# Sheet2.net
KiCad netlist of a schematic drawn in Altium Designer
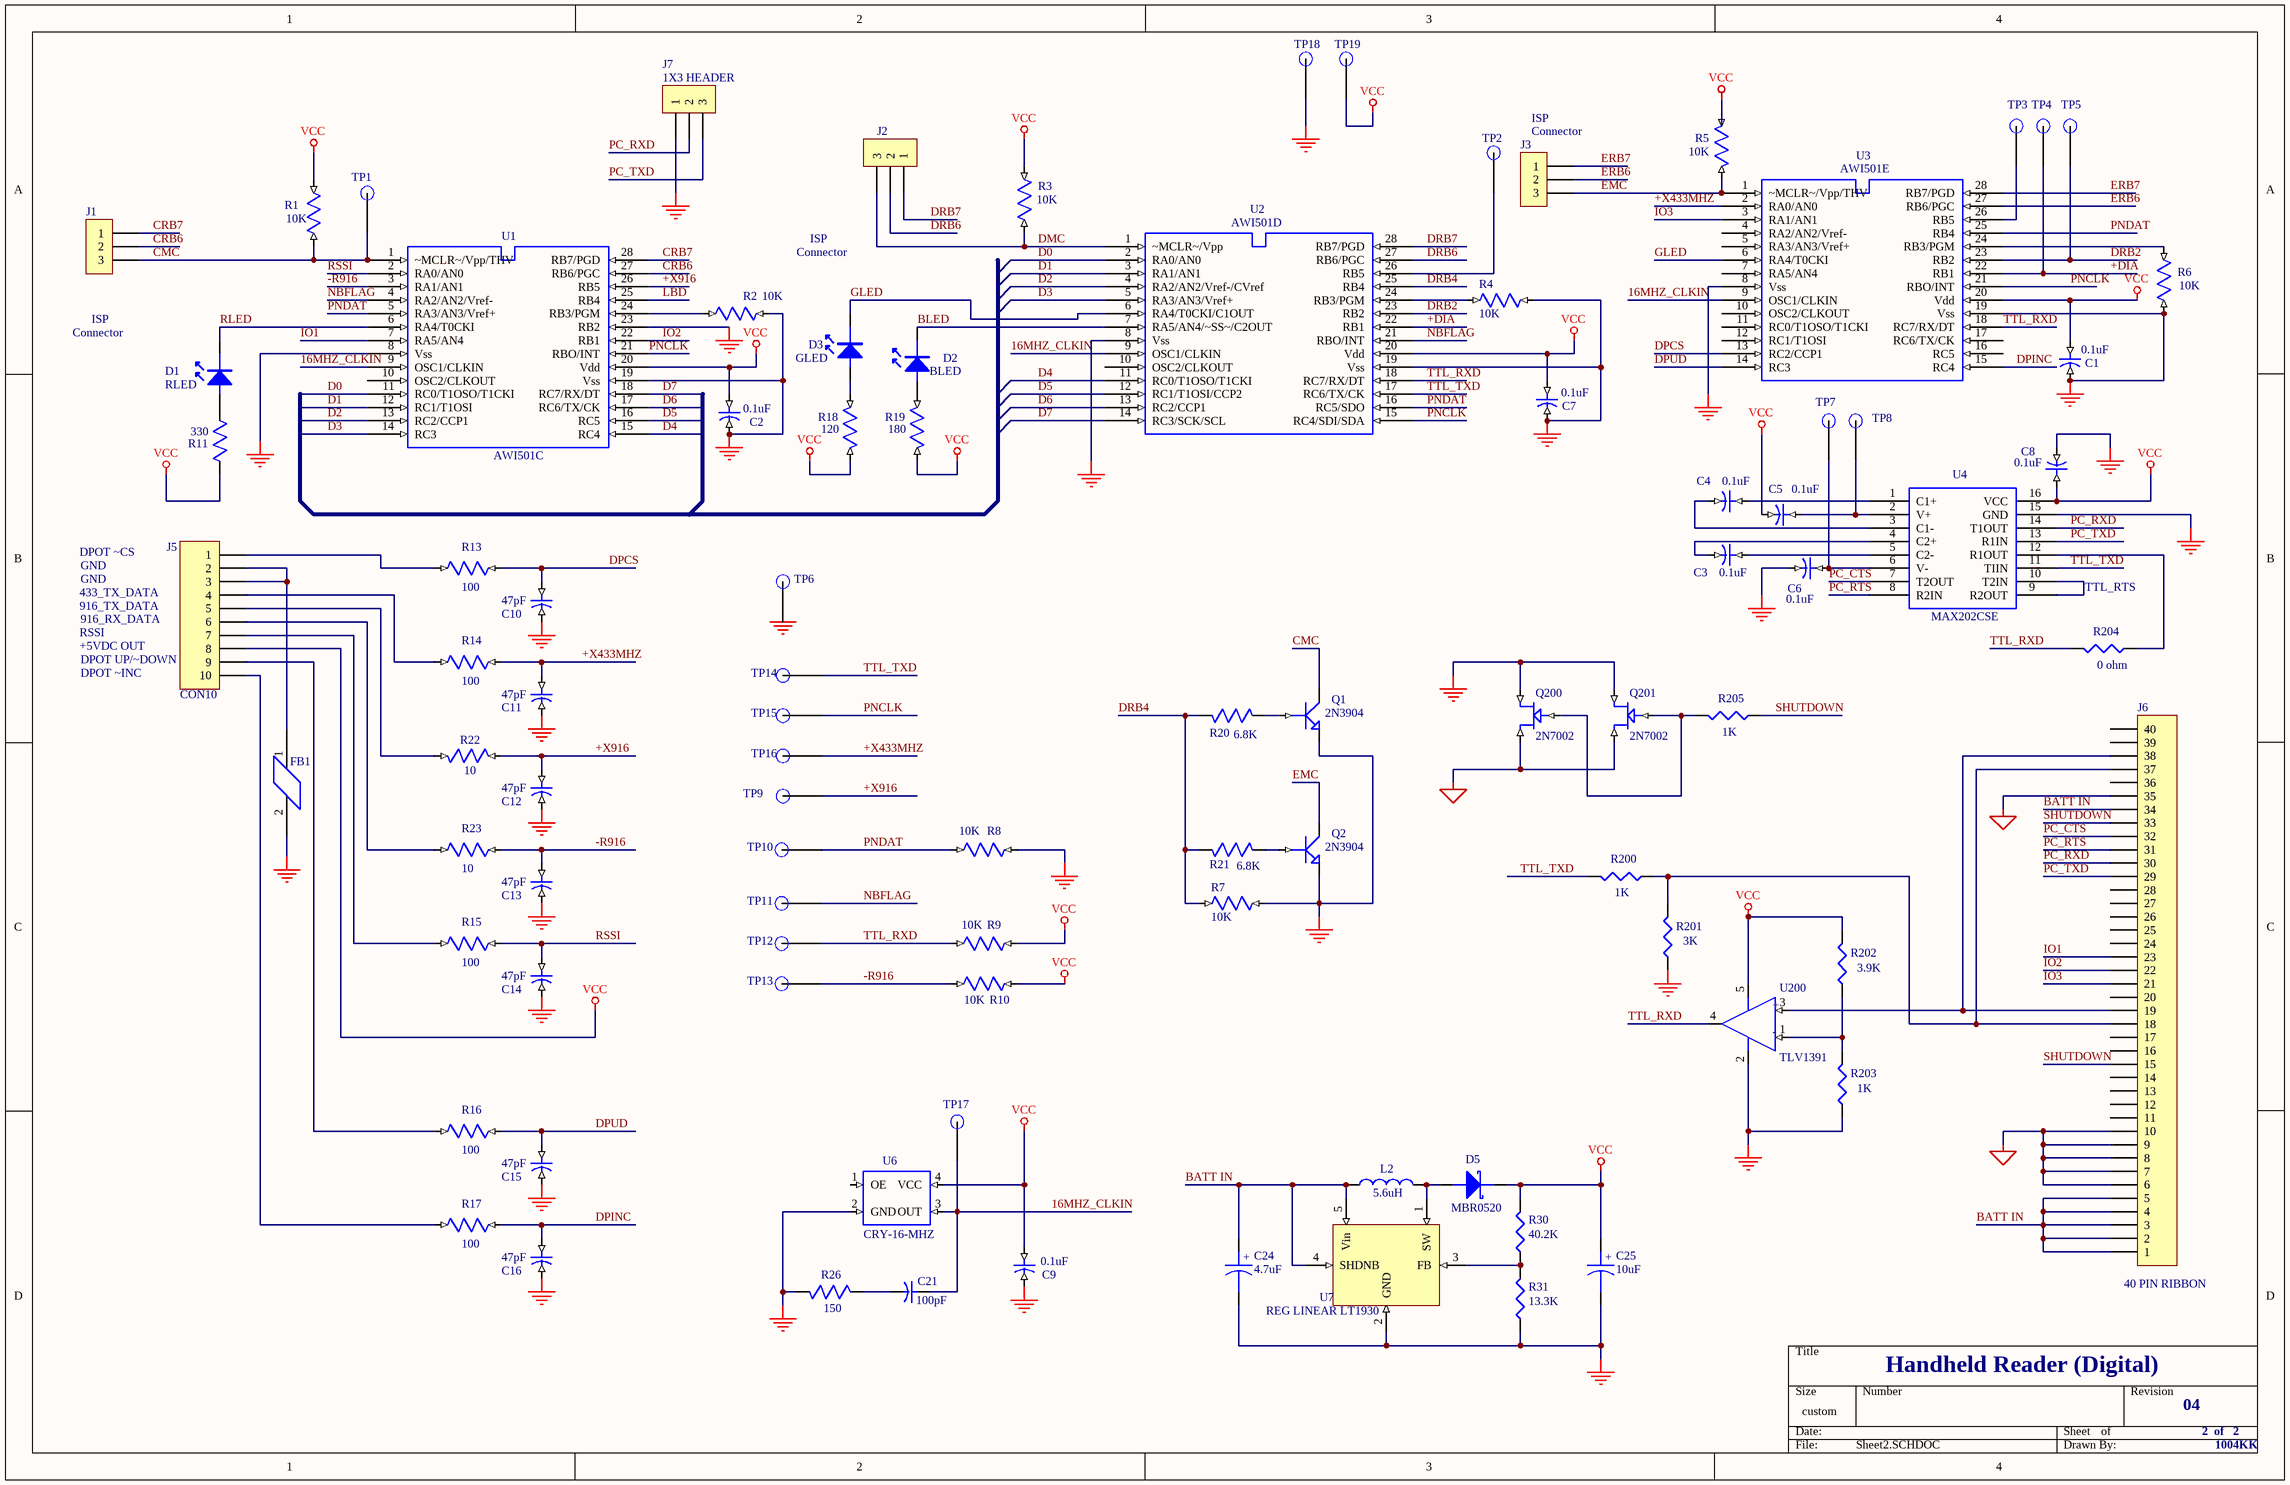
[diagram p0: Sheet2.SCHDOC]

(export (version "E")
  (design (tool "Eeschema 10.0.6"))
  (components
    (comp (ref "C1") (value "0.1uF") (footprint "0603") (libsource (lib "*") (part "C_603")))
    (comp (ref "C2") (value "0.1uF") (footprint "0603") (libsource (lib "*") (part "C_603")))
    (comp (ref "C3") (value "0.1uF") (footprint "0603") (libsource (lib "") (part "C_603_1")))
    (comp (ref "C4") (value "0.1uF") (footprint "0603") (libsource (lib "") (part "C_603_1")))
    (comp (ref "C5") (value "0.1uF") (footprint "0603") (libsource (lib "") (part "C_603_1")))
    (comp (ref "C6") (value "0.1uF") (footprint "0603") (libsource (lib "") (part "C_603_1")))
    (comp (ref "C7") (value "0.1uF") (footprint "0603") (libsource (lib "*") (part "C_603")))
    (comp (ref "C8") (value "0.1uF") (footprint "0603") (libsource (lib "") (part "C_603_1")))
    (comp (ref "C9") (value "0.1uF") (footprint "0603") (libsource (lib "") (part "C_603_1")))
    (comp (ref "C10") (value "47pF") (footprint "0603") (libsource (lib "*") (part "C0603")))
    (comp (ref "C11") (value "47pF") (footprint "0603") (libsource (lib "*") (part "C0603")))
    (comp (ref "C12") (value "47pF") (footprint "0603") (libsource (lib "*") (part "C0603")))
    (comp (ref "C13") (value "47pF") (footprint "0603") (libsource (lib "*") (part "C0603")))
    (comp (ref "C14") (value "47pF") (footprint "0603") (libsource (lib "*") (part "C0603")))
    (comp (ref "C15") (value "47pF") (footprint "0603") (libsource (lib "*") (part "C0603")))
    (comp (ref "C16") (value "47pF") (footprint "0603") (libsource (lib "*") (part "C0603")))
    (comp (ref "C21") (value "100pF") (footprint "0603") (libsource (lib "*") (part "C_0603")))
    (comp (ref "C24")
      (value "4.7uF")
      (footprint "CAP A CASE")
      (description "Capacitor")
      (libsource (lib "*") (part "CAPACITOR POL"))
    )
    (comp (ref "C25")
      (value "10uF")
      (footprint "CAP A CASE")
      (description "Capacitor")
      (libsource (lib "*") (part "CAPACITOR POL"))
    )
    (comp (ref "D1") (value "RLED") (footprint "SOD123 DIODE") (libsource (lib "*") (part "LED")))
    (comp (ref "D2") (value "BLED") (footprint "SOD123 DIODE") (libsource (lib "*") (part "LED")))
    (comp (ref "D3") (value "GLED") (footprint "SOD123 DIODE") (libsource (lib "*") (part "LED")))
    (comp (ref "D5")
      (value "MBR0520")
      (footprint "SOD123")
      (description "Schottky Diode")
      (libsource (lib "*") (part "DIODE SCHOTTKY"))
    )
    (comp (ref "FB1") (value "FB 0603") (footprint "0603") (libsource (lib "*") (part "FB_0603")))
    (comp (ref "J1")
      (value "1X3 HEADER")
      (footprint "1X3 HEADER")
      (description "Connector")
      (libsource (lib "*") (part "CON3"))
    )
    (comp (ref "J2")
      (value "1X3 HEADER")
      (footprint "1X3 HEADER")
      (description "Connector")
      (libsource (lib "") (part "CON3_2"))
    )
    (comp (ref "J3")
      (value "1X3 HEADER")
      (footprint "1X3 HEADER")
      (description "Connector")
      (libsource (lib "*") (part "CON3"))
    )
    (comp (ref "J5")
      (value "CON10")
      (footprint "1X10 HEADER SPECIAL")
      (description "Connector")
      (libsource (lib "*") (part "CON10"))
    )
    (comp (ref "J6")
      (value "40 PIN RIBBON")
      (footprint "40 PIN RIBBON CONN")
      (description "Connector")
      (libsource (lib "*") (part "CON40"))
    )
    (comp (ref "J7")
      (value "1X3 HEADER")
      (footprint "1X3 HEADER")
      (description "Connector")
      (libsource (lib "") (part "CON3_1"))
    )
    (comp (ref "L2")
      (value "5.6uH")
      (footprint "COIL BOURNS SDR7030-330M")
      (libsource (lib "*") (part "INDUCTOR1"))
    )
    (comp (ref "Q1")
      (value "2N3904")
      (footprint "SOT23 TRANS")
      (description "NPN Transistor")
      (libsource (lib "*") (part "NPN1"))
    )
    (comp (ref "Q2")
      (value "2N3904")
      (footprint "SOT23 TRANS")
      (description "NPN Transistor")
      (libsource (lib "*") (part "NPN1"))
    )
    (comp (ref "Q200") (value "2N7002") (footprint "SOT23 FET") (libsource (lib "*") (part "JFET N")))
    (comp (ref "Q201") (value "2N7002") (footprint "SOT23 FET") (libsource (lib "*") (part "JFET N")))
    (comp (ref "R1") (value "10K") (footprint "0603") (libsource (lib "*") (part "R_603")))
    (comp (ref "R2") (value "10K") (footprint "0603") (libsource (lib "*") (part "R_603")))
    (comp (ref "R3") (value "10K") (footprint "0603") (libsource (lib "*") (part "R_603")))
    (comp (ref "R4") (value "10K") (footprint "0603") (libsource (lib "*") (part "R_603")))
    (comp (ref "R5") (value "10K") (footprint "0603") (libsource (lib "*") (part "R_603")))
    (comp (ref "R6") (value "10K") (footprint "0603") (libsource (lib "*") (part "R_603")))
    (comp (ref "R7") (value "10K") (footprint "0603") (libsource (lib "*") (part "R_603")))
    (comp (ref "R8") (value "10K") (footprint "0603") (libsource (lib "*") (part "R_603")))
    (comp (ref "R9") (value "10K") (footprint "0603") (libsource (lib "*") (part "R_603")))
    (comp (ref "R10") (value "10K") (footprint "0603") (libsource (lib "*") (part "R_603")))
    (comp (ref "R11") (value "330") (footprint "0603") (libsource (lib "*") (part "R_0603")))
    (comp (ref "R13") (value "100") (footprint "0603") (libsource (lib "*") (part "R0603")))
    (comp (ref "R14") (value "100") (footprint "0603") (libsource (lib "*") (part "R0603")))
    (comp (ref "R15") (value "100") (footprint "0603") (libsource (lib "*") (part "R0603")))
    (comp (ref "R16") (value "100") (footprint "0603") (libsource (lib "*") (part "R0603")))
    (comp (ref "R17") (value "100") (footprint "0603") (libsource (lib "*") (part "R0603")))
    (comp (ref "R18") (value "120") (footprint "0603") (libsource (lib "*") (part "R0402")))
    (comp (ref "R19") (value "180") (footprint "0603") (libsource (lib "*") (part "R0402")))
    (comp (ref "R20") (value "6.8K") (footprint "0603") (libsource (lib "*") (part "R_0603")))
    (comp (ref "R21") (value "6.8K") (footprint "0603") (libsource (lib "*") (part "R_0603")))
    (comp (ref "R22") (value "10") (footprint "0603") (libsource (lib "*") (part "R_603")))
    (comp (ref "R23") (value "10") (footprint "0603") (libsource (lib "*") (part "R0603")))
    (comp (ref "R26") (value "150") (footprint "0603") (libsource (lib "*") (part "R_0603")))
    (comp (ref "R30") (value "40.2K") (footprint "0603") (libsource (lib "*") (part "RES1")))
    (comp (ref "R31") (value "13.3K") (footprint "0603") (libsource (lib "*") (part "RES1")))
    (comp (ref "R200") (value "1K") (footprint "0603") (libsource (lib "*") (part "RES1")))
    (comp (ref "R201") (value "3K") (footprint "0603") (libsource (lib "*") (part "RES1")))
    (comp (ref "R202") (value "3.9K") (footprint "0603") (libsource (lib "*") (part "RES1")))
    (comp (ref "R203") (value "1K") (footprint "0603") (libsource (lib "*") (part "RES1")))
    (comp (ref "R204") (value "0 ohm") (footprint "0603") (libsource (lib "*") (part "RES1")))
    (comp (ref "R205") (value "1K") (footprint "0603") (libsource (lib "*") (part "RES1")))
    (comp (ref "TP1") (value "TP") (footprint "TEST POINT PAD") (libsource (lib "*") (part "TESTPOINT_1")))
    (comp (ref "TP2") (value "TP") (footprint "TEST POINT PAD") (libsource (lib "*") (part "TESTPOINT_1")))
    (comp (ref "TP3") (value "TP") (footprint "TEST POINT PAD") (libsource (lib "*") (part "TESTPOINT_1")))
    (comp (ref "TP4") (value "TP") (footprint "TEST POINT PAD") (libsource (lib "*") (part "TESTPOINT_1")))
    (comp (ref "TP5") (value "TP") (footprint "TEST POINT PAD") (libsource (lib "*") (part "TESTPOINT_1")))
    (comp (ref "TP6") (value "TP") (footprint "TEST POINT PAD") (libsource (lib "*") (part "TESTPOINT_1")))
    (comp (ref "TP7") (value "TP") (footprint "TEST POINT PAD") (libsource (lib "*") (part "TESTPOINT_1")))
    (comp (ref "TP8") (value "TP") (footprint "TEST POINT PAD") (libsource (lib "*") (part "TESTPOINT_1")))
    (comp (ref "TP9") (value "TP") (footprint "TEST POINT PAD") (libsource (lib "*") (part "TESTPOINT_1")))
    (comp (ref "TP10") (value "TP") (footprint "TEST POINT PAD") (libsource (lib "*") (part "TESTPOINT_1")))
    (comp (ref "TP11") (value "TP") (footprint "TEST POINT PAD") (libsource (lib "*") (part "TESTPOINT_1")))
    (comp (ref "TP12") (value "TP") (footprint "TEST POINT PAD") (libsource (lib "*") (part "TESTPOINT_1")))
    (comp (ref "TP13") (value "TP") (footprint "TEST POINT PAD") (libsource (lib "*") (part "TESTPOINT_1")))
    (comp (ref "TP14") (value "TP") (footprint "TEST POINT PAD") (libsource (lib "*") (part "TESTPOINT_1")))
    (comp (ref "TP15") (value "TP") (footprint "TEST POINT PAD") (libsource (lib "*") (part "TESTPOINT_1")))
    (comp (ref "TP16") (value "TP") (footprint "TEST POINT PAD") (libsource (lib "*") (part "TESTPOINT_1")))
    (comp (ref "TP17") (value "TP") (footprint "TEST POINT PAD") (libsource (lib "*") (part "TESTPOINT_1")))
    (comp (ref "TP18") (value "TP") (footprint "TEST POINT PAD") (libsource (lib "*") (part "TESTPOINT_1")))
    (comp (ref "TP19") (value "TP") (footprint "TEST POINT PAD") (libsource (lib "*") (part "TESTPOINT_1")))
    (comp (ref "U1") (value "AWI501C") (footprint "SSOP28") (libsource (lib "*") (part "PIC16F870")))
    (comp (ref "U2") (value "AWI501D") (footprint "SSOP28") (libsource (lib "*") (part "PIC16F876A")))
    (comp (ref "U3") (value "AWI501E") (footprint "SSOP28") (libsource (lib "*") (part "PIC16F870")))
    (comp (ref "U4") (value "MAX202CSE") (footprint "SO16") (libsource (lib "*") (part "MAX202CSE")))
    (comp (ref "U6")
      (value "CRY-16-MHZ")
      (footprint "SMT OSCILLATOR")
      (libsource (lib "*") (part "CRY-SMD-5-7"))
    )
    (comp (ref "U7")
      (value "REG LINEAR LT1930")
      (footprint "SOT23-5A")
      (libsource (lib "*") (part "REG LINEAR LT1930"))
    )
    (comp (ref "U200") (value "TLV1391") (footprint "SOT25") (libsource (lib "*") (part "TLV1391")))
  )
  (nets
    (net (code "1") (name "/+DIA") (class "Default")
      (node (ref "TP4") (pin "1") (pinfunction "TP_1") (pintype "passive"))
      (node (ref "U2") (pin "22") (pinfunction "RB1_22") (pintype "input"))
      (node (ref "U3") (pin "22") (pinfunction "RB1_22") (pintype "input"))
    )
    (net (code "2") (name "/+X433MHZ") (class "Default")
      (node (ref "C11") (pin "1") (pinfunction "A_1") (pintype "input"))
      (node (ref "R14") (pin "2") (pinfunction "B_2") (pintype "input"))
      (node (ref "TP16") (pin "1") (pinfunction "TP_1") (pintype "passive"))
      (node (ref "U3") (pin "2") (pinfunction "RA0/AN0_2") (pintype "input"))
    )
    (net (code "3") (name "/+X916") (class "Default")
      (node (ref "C12") (pin "1") (pinfunction "A_1") (pintype "input"))
      (node (ref "R22") (pin "1") (pinfunction "A_1") (pintype "input"))
      (node (ref "TP9") (pin "1") (pinfunction "TP_1") (pintype "passive"))
      (node (ref "U1") (pin "26") (pinfunction "RB5_26") (pintype "input"))
    )
    (net (code "4") (name "/-R916") (class "Default")
      (node (ref "C13") (pin "1") (pinfunction "A_1") (pintype "input"))
      (node (ref "R10") (pin "2") (pinfunction "B_2") (pintype "input"))
      (node (ref "R23") (pin "2") (pinfunction "B_2") (pintype "input"))
      (node (ref "TP13") (pin "1") (pinfunction "TP_1") (pintype "passive"))
      (node (ref "U1") (pin "3") (pinfunction "RA1/AN1_3") (pintype "input"))
    )
    (net (code "5") (name "/16MHZ_CLKIN") (class "Default")
      (node (ref "C21") (pin "1") (pinfunction "A_1") (pintype "passive"))
      (node (ref "TP17") (pin "1") (pinfunction "TP_1") (pintype "passive"))
      (node (ref "U1") (pin "9") (pinfunction "OSC1/CLKIN_9") (pintype "input"))
      (node (ref "U2") (pin "9") (pinfunction "OSC1/CLKIN_9") (pintype "input"))
      (node (ref "U3") (pin "9") (pinfunction "OSC1/CLKIN_9") (pintype "input"))
      (node (ref "U6") (pin "3") (pinfunction "OUT_3") (pintype "input"))
    )
    (net (code "6") (name "/BATT IN") (class "Default")
      (node (ref "C24") (pin "1") (pinfunction "1_1") (pintype "passive"))
      (node (ref "J6") (pin "1") (pinfunction "1_1") (pintype "passive"))
      (node (ref "J6") (pin "2") (pinfunction "2_2") (pintype "passive"))
      (node (ref "J6") (pin "3") (pinfunction "3_3") (pintype "passive"))
      (node (ref "J6") (pin "34") (pinfunction "34_34") (pintype "passive"))
      (node (ref "J6") (pin "4") (pinfunction "4_4") (pintype "passive"))
      (node (ref "J6") (pin "5") (pinfunction "5_5") (pintype "passive"))
      (node (ref "L2") (pin "1") (pinfunction "1_1") (pintype "passive"))
      (node (ref "U7") (pin "4") (pinfunction "SHDNB_4") (pintype "input"))
      (node (ref "U7") (pin "5") (pinfunction "Vin_5") (pintype "input"))
    )
    (net (code "7") (name "/BLED") (class "Default")
      (node (ref "D2") (pin "K") (pinfunction "K_K") (pintype "passive"))
      (node (ref "U2") (pin "7") (pinfunction "RA5/AN4/~SS~/C2OUT_7") (pintype "input"))
    )
    (net (code "8") (name "/CMC") (class "Default")
      (node (ref "J1") (pin "3") (pinfunction "3_3") (pintype "passive"))
      (node (ref "Q1") (pin "C") (pinfunction "C_C") (pintype "passive"))
      (node (ref "R1") (pin "2") (pinfunction "B_2") (pintype "input"))
      (node (ref "TP1") (pin "1") (pinfunction "TP_1") (pintype "passive"))
      (node (ref "U1") (pin "1") (pinfunction "~MCLR~/Vpp/THV_1") (pintype "input"))
    )
    (net (code "9") (name "/CRB6") (class "Default")
      (node (ref "J1") (pin "2") (pinfunction "2_2") (pintype "passive"))
      (node (ref "U1") (pin "27") (pinfunction "RB6/PGC_27") (pintype "input"))
    )
    (net (code "10") (name "/CRB7") (class "Default")
      (node (ref "J1") (pin "1") (pinfunction "1_1") (pintype "passive"))
      (node (ref "U1") (pin "28") (pinfunction "RB7/PGD_28") (pintype "input"))
    )
    (net (code "11") (name "/D0") (class "Default")
      (node (ref "U1") (pin "11") (pinfunction "RC0/T1OSO/T1CKI_11") (pintype "input"))
      (node (ref "U2") (pin "2") (pinfunction "RA0/AN0_2") (pintype "input"))
    )
    (net (code "12") (name "/D1") (class "Default")
      (node (ref "U1") (pin "12") (pinfunction "RC1/T1OSI_12") (pintype "input"))
      (node (ref "U2") (pin "3") (pinfunction "RA1/AN1_3") (pintype "input"))
    )
    (net (code "13") (name "/D2") (class "Default")
      (node (ref "U1") (pin "13") (pinfunction "RC2/CCP1_13") (pintype "input"))
      (node (ref "U2") (pin "4") (pinfunction "RA2/AN2/Vref-/CVref_4") (pintype "input"))
    )
    (net (code "14") (name "/D3") (class "Default")
      (node (ref "U1") (pin "14") (pinfunction "RC3_14") (pintype "input"))
      (node (ref "U2") (pin "5") (pinfunction "RA3/AN3/Vref+_5") (pintype "input"))
    )
    (net (code "15") (name "/D4") (class "Default")
      (node (ref "U1") (pin "15") (pinfunction "RC4_15") (pintype "input"))
      (node (ref "U2") (pin "11") (pinfunction "RC0/T1OSO/T1CKI_11") (pintype "input"))
    )
    (net (code "16") (name "/D5") (class "Default")
      (node (ref "U1") (pin "16") (pinfunction "RC5_16") (pintype "input"))
      (node (ref "U2") (pin "12") (pinfunction "RC1/T1OSI/CCP2_12") (pintype "input"))
    )
    (net (code "17") (name "/D6") (class "Default")
      (node (ref "U1") (pin "17") (pinfunction "RC6/TX/CK_17") (pintype "input"))
      (node (ref "U2") (pin "13") (pinfunction "RC2/CCP1_13") (pintype "input"))
    )
    (net (code "18") (name "/D7") (class "Default")
      (node (ref "U1") (pin "18") (pinfunction "RC7/RX/DT_18") (pintype "input"))
      (node (ref "U2") (pin "14") (pinfunction "RC3/SCK/SCL_14") (pintype "input"))
    )
    (net (code "19") (name "/DMC") (class "Default")
      (node (ref "J2") (pin "3") (pinfunction "3_3") (pintype "passive"))
      (node (ref "R3") (pin "2") (pinfunction "B_2") (pintype "input"))
      (node (ref "U2") (pin "1") (pinfunction "~MCLR~/Vpp_1") (pintype "input"))
    )
    (net (code "20") (name "/DPCS") (class "Default")
      (node (ref "C10") (pin "1") (pinfunction "A_1") (pintype "input"))
      (node (ref "R13") (pin "2") (pinfunction "B_2") (pintype "input"))
      (node (ref "U3") (pin "13") (pinfunction "RC2/CCP1_13") (pintype "input"))
    )
    (net (code "21") (name "/DPINC") (class "Default")
      (node (ref "C16") (pin "1") (pinfunction "A_1") (pintype "input"))
      (node (ref "R17") (pin "2") (pinfunction "B_2") (pintype "input"))
      (node (ref "U3") (pin "15") (pinfunction "RC4_15") (pintype "input"))
    )
    (net (code "22") (name "/DPUD") (class "Default")
      (node (ref "C15") (pin "1") (pinfunction "A_1") (pintype "input"))
      (node (ref "R16") (pin "2") (pinfunction "B_2") (pintype "input"))
      (node (ref "U3") (pin "14") (pinfunction "RC3_14") (pintype "input"))
    )
    (net (code "23") (name "/DRB2") (class "Default")
      (node (ref "TP5") (pin "1") (pinfunction "TP_1") (pintype "passive"))
      (node (ref "U2") (pin "23") (pinfunction "RB2_23") (pintype "input"))
      (node (ref "U3") (pin "23") (pinfunction "RB2_23") (pintype "input"))
    )
    (net (code "24") (name "/DRB4") (class "Default")
      (node (ref "R20") (pin "1") (pinfunction "A_1") (pintype "passive"))
      (node (ref "R21") (pin "1") (pinfunction "A_1") (pintype "passive"))
      (node (ref "R7") (pin "1") (pinfunction "A_1") (pintype "input"))
      (node (ref "U2") (pin "25") (pinfunction "RB4_25") (pintype "input"))
    )
    (net (code "25") (name "/DRB6") (class "Default")
      (node (ref "J2") (pin "2") (pinfunction "2_2") (pintype "passive"))
      (node (ref "U2") (pin "27") (pinfunction "RB6/PGC_27") (pintype "input"))
    )
    (net (code "26") (name "/DRB7") (class "Default")
      (node (ref "J2") (pin "1") (pinfunction "1_1") (pintype "passive"))
      (node (ref "U2") (pin "28") (pinfunction "RB7/PGD_28") (pintype "input"))
    )
    (net (code "27") (name "/EMC") (class "Default")
      (node (ref "J3") (pin "3") (pinfunction "3_3") (pintype "passive"))
      (node (ref "Q2") (pin "C") (pinfunction "C_C") (pintype "passive"))
      (node (ref "R5") (pin "2") (pinfunction "B_2") (pintype "input"))
      (node (ref "U3") (pin "1") (pinfunction "~MCLR~/Vpp/THV_1") (pintype "input"))
    )
    (net (code "28") (name "/ERB6") (class "Default")
      (node (ref "J3") (pin "2") (pinfunction "2_2") (pintype "passive"))
      (node (ref "U3") (pin "27") (pinfunction "RB6/PGC_27") (pintype "input"))
    )
    (net (code "29") (name "/ERB7") (class "Default")
      (node (ref "J3") (pin "1") (pinfunction "1_1") (pintype "passive"))
      (node (ref "U3") (pin "28") (pinfunction "RB7/PGD_28") (pintype "input"))
    )
    (net (code "30") (name "/GLED") (class "Default")
      (node (ref "D3") (pin "K") (pinfunction "K_K") (pintype "passive"))
      (node (ref "U2") (pin "6") (pinfunction "RA4/T0CKI/C1OUT_6") (pintype "input"))
      (node (ref "U3") (pin "6") (pinfunction "RA4/T0CKI_6") (pintype "input"))
    )
    (net (code "31") (name "/IO1") (class "Default")
      (node (ref "J6") (pin "23") (pinfunction "23_23") (pintype "passive"))
      (node (ref "U1") (pin "7") (pinfunction "RA5/AN4_7") (pintype "input"))
    )
    (net (code "32") (name "/IO2") (class "Default")
      (node (ref "J6") (pin "22") (pinfunction "22_22") (pintype "passive"))
      (node (ref "U1") (pin "22") (pinfunction "RB1_22") (pintype "input"))
    )
    (net (code "33") (name "/IO3") (class "Default")
      (node (ref "J6") (pin "21") (pinfunction "21_21") (pintype "passive"))
      (node (ref "U3") (pin "3") (pinfunction "RA1/AN1_3") (pintype "input"))
    )
    (net (code "34") (name "/LBD") (class "Default")
      (node (ref "U1") (pin "25") (pinfunction "RB4_25") (pintype "input"))
    )
    (net (code "35") (name "/NBFLAG") (class "Default")
      (node (ref "TP11") (pin "1") (pinfunction "TP_1") (pintype "passive"))
      (node (ref "U1") (pin "4") (pinfunction "RA2/AN2/Vref-_4") (pintype "input"))
      (node (ref "U2") (pin "21") (pinfunction "RBO/INT_21") (pintype "input"))
    )
    (net (code "36") (name "/PC_CTS") (class "Default")
      (node (ref "J6") (pin "32") (pinfunction "32_32") (pintype "passive"))
      (node (ref "U4") (pin "7") (pinfunction "T2OUT_7") (pintype "passive"))
    )
    (net (code "37") (name "/PC_RTS") (class "Default")
      (node (ref "J6") (pin "31") (pinfunction "31_31") (pintype "passive"))
      (node (ref "U4") (pin "8") (pinfunction "R2IN_8") (pintype "passive"))
    )
    (net (code "38") (name "/PC_RXD") (class "Default")
      (node (ref "J6") (pin "30") (pinfunction "30_30") (pintype "passive"))
      (node (ref "J7") (pin "2") (pinfunction "2_2") (pintype "passive"))
      (node (ref "U4") (pin "14") (pinfunction "T1OUT_14") (pintype "passive"))
    )
    (net (code "39") (name "/PC_TXD") (class "Default")
      (node (ref "J6") (pin "29") (pinfunction "29_29") (pintype "passive"))
      (node (ref "J7") (pin "3") (pinfunction "3_3") (pintype "passive"))
      (node (ref "U4") (pin "13") (pinfunction "R1IN_13") (pintype "passive"))
    )
    (net (code "40") (name "/PNCLK") (class "Default")
      (node (ref "TP15") (pin "1") (pinfunction "TP_1") (pintype "passive"))
      (node (ref "U1") (pin "21") (pinfunction "RBO/INT_21") (pintype "input"))
      (node (ref "U2") (pin "15") (pinfunction "RC4/SDI/SDA_15") (pintype "input"))
      (node (ref "U3") (pin "21") (pinfunction "RBO/INT_21") (pintype "input"))
    )
    (net (code "41") (name "/PNDAT") (class "Default")
      (node (ref "R8") (pin "2") (pinfunction "B_2") (pintype "input"))
      (node (ref "TP10") (pin "1") (pinfunction "TP_1") (pintype "passive"))
      (node (ref "U1") (pin "5") (pinfunction "RA3/AN3/Vref+_5") (pintype "input"))
      (node (ref "U2") (pin "16") (pinfunction "RC5/SDO_16") (pintype "input"))
      (node (ref "U3") (pin "25") (pinfunction "RB4_25") (pintype "input"))
    )
    (net (code "42") (name "/RLED") (class "Default")
      (node (ref "D1") (pin "K") (pinfunction "K_K") (pintype "passive"))
      (node (ref "U1") (pin "6") (pinfunction "RA4/T0CKI_6") (pintype "input"))
    )
    (net (code "43") (name "/RSSI") (class "Default")
      (node (ref "C14") (pin "1") (pinfunction "A_1") (pintype "input"))
      (node (ref "R15") (pin "2") (pinfunction "B_2") (pintype "input"))
      (node (ref "U1") (pin "2") (pinfunction "RA0/AN0_2") (pintype "input"))
    )
    (net (code "44") (name "/SHUTDOWN") (class "Default")
      (node (ref "J6") (pin "15") (pinfunction "15_15") (pintype "passive"))
      (node (ref "J6") (pin "33") (pinfunction "33_33") (pintype "passive"))
      (node (ref "R205") (pin "1") (pinfunction "1_1") (pintype "passive"))
    )
    (net (code "45") (name "/TTL_RXD") (class "Default")
      (node (ref "R204") (pin "2") (pinfunction "2_2") (pintype "passive"))
      (node (ref "R9") (pin "2") (pinfunction "B_2") (pintype "input"))
      (node (ref "TP12") (pin "1") (pinfunction "TP_1") (pintype "passive"))
      (node (ref "U2") (pin "18") (pinfunction "RC7/RX/DT_18") (pintype "input"))
      (node (ref "U200") (pin "4") (pinfunction "OUT_4") (pintype "open_collector"))
      (node (ref "U3") (pin "18") (pinfunction "RC7/RX/DT_18") (pintype "input"))
    )
    (net (code "46") (name "/TTL_TXD") (class "Default")
      (node (ref "R200") (pin "2") (pinfunction "2_2") (pintype "passive"))
      (node (ref "TP14") (pin "1") (pinfunction "TP_1") (pintype "passive"))
      (node (ref "U2") (pin "17") (pinfunction "RC6/TX/CK_17") (pintype "input"))
      (node (ref "U4") (pin "11") (pinfunction "TIIN_11") (pintype "passive"))
    )
    (net (code "47") (name "GND1") (class "Default")
      (node (ref "J6") (pin "10") (pinfunction "10_10") (pintype "passive"))
      (node (ref "J6") (pin "35") (pinfunction "35_35") (pintype "passive"))
      (node (ref "J6") (pin "6") (pinfunction "6_6") (pintype "passive"))
      (node (ref "J6") (pin "7") (pinfunction "7_7") (pintype "passive"))
      (node (ref "J6") (pin "8") (pinfunction "8_8") (pintype "passive"))
      (node (ref "J6") (pin "9") (pinfunction "9_9") (pintype "passive"))
      (node (ref "Q200") (pin "S") (pinfunction "S_S") (pintype "input"))
      (node (ref "Q201") (pin "S") (pinfunction "S_S") (pintype "input"))
    )
    (net (code "48") (name "GND_COM") (class "Default")
      (node (ref "C1") (pin "2") (pinfunction "B_2") (pintype "input"))
      (node (ref "C10") (pin "2") (pinfunction "B_2") (pintype "input"))
      (node (ref "C11") (pin "2") (pinfunction "B_2") (pintype "input"))
      (node (ref "C12") (pin "2") (pinfunction "B_2") (pintype "input"))
      (node (ref "C13") (pin "2") (pinfunction "B_2") (pintype "input"))
      (node (ref "C14") (pin "2") (pinfunction "B_2") (pintype "input"))
      (node (ref "C15") (pin "2") (pinfunction "B_2") (pintype "input"))
      (node (ref "C16") (pin "2") (pinfunction "B_2") (pintype "input"))
      (node (ref "C2") (pin "2") (pinfunction "B_2") (pintype "input"))
      (node (ref "C24") (pin "2") (pinfunction "2_2") (pintype "passive"))
      (node (ref "C25") (pin "2") (pinfunction "2_2") (pintype "passive"))
      (node (ref "C6") (pin "2") (pinfunction "B_2") (pintype "input"))
      (node (ref "C7") (pin "2") (pinfunction "B_2") (pintype "input"))
      (node (ref "C8") (pin "2") (pinfunction "B_2") (pintype "input"))
      (node (ref "C9") (pin "2") (pinfunction "B_2") (pintype "input"))
      (node (ref "FB1") (pin "2") (pinfunction "1_2") (pintype "passive"))
      (node (ref "J7") (pin "1") (pinfunction "1_1") (pintype "passive"))
      (node (ref "Q1") (pin "E") (pinfunction "E_E") (pintype "passive"))
      (node (ref "Q2") (pin "E") (pinfunction "E_E") (pintype "passive"))
      (node (ref "Q200") (pin "D") (pinfunction "D_D") (pintype "input"))
      (node (ref "Q201") (pin "D") (pinfunction "D_D") (pintype "input"))
      (node (ref "R2") (pin "2") (pinfunction "B_2") (pintype "input"))
      (node (ref "R201") (pin "1") (pinfunction "1_1") (pintype "passive"))
      (node (ref "R203") (pin "1") (pinfunction "1_1") (pintype "passive"))
      (node (ref "R26") (pin "2") (pinfunction "B_2") (pintype "passive"))
      (node (ref "R31") (pin "1") (pinfunction "1_1") (pintype "passive"))
      (node (ref "R4") (pin "1") (pinfunction "A_1") (pintype "input"))
      (node (ref "R6") (pin "2") (pinfunction "B_2") (pintype "input"))
      (node (ref "R7") (pin "2") (pinfunction "B_2") (pintype "input"))
      (node (ref "R8") (pin "1") (pinfunction "A_1") (pintype "input"))
      (node (ref "TP18") (pin "1") (pinfunction "TP_1") (pintype "passive"))
      (node (ref "TP6") (pin "1") (pinfunction "TP_1") (pintype "passive"))
      (node (ref "U1") (pin "19") (pinfunction "Vss_19") (pintype "input"))
      (node (ref "U1") (pin "23") (pinfunction "RB2_23") (pintype "input"))
      (node (ref "U1") (pin "8") (pinfunction "Vss_8") (pintype "input"))
      (node (ref "U2") (pin "19") (pinfunction "Vss_19") (pintype "input"))
      (node (ref "U2") (pin "8") (pinfunction "Vss_8") (pintype "input"))
      (node (ref "U200") (pin "2") (pinfunction "VSS_2") (pintype "power_in"))
      (node (ref "U3") (pin "19") (pinfunction "Vss_19") (pintype "input"))
      (node (ref "U3") (pin "8") (pinfunction "Vss_8") (pintype "input"))
      (node (ref "U4") (pin "15") (pinfunction "GND_15") (pintype "passive"))
      (node (ref "U6") (pin "2") (pinfunction "GND_2") (pintype "input"))
      (node (ref "U7") (pin "2") (pinfunction "GND_2") (pintype "input"))
    )
    (net (code "49") (name "Net-(C3-A)") (class "Default")
      (node (ref "C3") (pin "1") (pinfunction "A_1") (pintype "input"))
      (node (ref "U4") (pin "5") (pinfunction "C2-_5") (pintype "passive"))
    )
    (net (code "50") (name "Net-(C3-B)") (class "Default")
      (node (ref "C3") (pin "2") (pinfunction "B_2") (pintype "input"))
      (node (ref "U4") (pin "4") (pinfunction "C2+_4") (pintype "passive"))
    )
    (net (code "51") (name "Net-(C4-A)") (class "Default")
      (node (ref "C4") (pin "1") (pinfunction "A_1") (pintype "input"))
      (node (ref "U4") (pin "1") (pinfunction "C1+_1") (pintype "passive"))
    )
    (net (code "52") (name "Net-(C4-B)") (class "Default")
      (node (ref "C4") (pin "2") (pinfunction "B_2") (pintype "input"))
      (node (ref "U4") (pin "3") (pinfunction "C1-_3") (pintype "passive"))
    )
    (net (code "53") (name "Net-(C5-A)") (class "Default")
      (node (ref "C5") (pin "1") (pinfunction "A_1") (pintype "input"))
      (node (ref "TP8") (pin "1") (pinfunction "TP_1") (pintype "passive"))
      (node (ref "U4") (pin "2") (pinfunction "V+_2") (pintype "passive"))
    )
    (net (code "54") (name "Net-(C6-A)") (class "Default")
      (node (ref "C6") (pin "1") (pinfunction "A_1") (pintype "input"))
      (node (ref "TP7") (pin "1") (pinfunction "TP_1") (pintype "passive"))
      (node (ref "U4") (pin "6") (pinfunction "V-_6") (pintype "passive"))
    )
    (net (code "55") (name "Net-(C21-B)") (class "Default")
      (node (ref "C21") (pin "2") (pinfunction "B_2") (pintype "passive"))
      (node (ref "R26") (pin "1") (pinfunction "A_1") (pintype "passive"))
    )
    (net (code "56") (name "Net-(FB1-2)") (class "Default")
      (node (ref "FB1") (pin "1") (pinfunction "2_1") (pintype "passive"))
      (node (ref "J5") (pin "2") (pinfunction "2_2") (pintype "passive"))
      (node (ref "J5") (pin "3") (pinfunction "3_3") (pintype "passive"))
    )
    (net (code "57") (name "Net-(J6-Pad18)") (class "Default")
      (node (ref "J6") (pin "18") (pinfunction "18_18") (pintype "passive"))
      (node (ref "J6") (pin "37") (pinfunction "37_37") (pintype "passive"))
      (node (ref "R200") (pin "1") (pinfunction "1_1") (pintype "passive"))
      (node (ref "R201") (pin "2") (pinfunction "2_2") (pintype "passive"))
    )
    (net (code "58") (name "Net-(Q200-PadG)") (class "Default")
      (node (ref "Q200") (pin "G") (pinfunction "G_G") (pintype "input"))
      (node (ref "Q201") (pin "G") (pinfunction "G_G") (pintype "input"))
      (node (ref "R205") (pin "2") (pinfunction "2_2") (pintype "passive"))
    )
    (net (code "59") (name "Net-(R2-A)") (class "Default")
      (node (ref "R2") (pin "1") (pinfunction "A_1") (pintype "input"))
      (node (ref "U1") (pin "24") (pinfunction "RB3/PGM_24") (pintype "input"))
    )
    (net (code "60") (name "Net-(R4-B)") (class "Default")
      (node (ref "R4") (pin "2") (pinfunction "B_2") (pintype "input"))
      (node (ref "U2") (pin "24") (pinfunction "RB3/PGM_24") (pintype "input"))
    )
    (net (code "61") (name "Net-(R6-A)") (class "Default")
      (node (ref "R6") (pin "1") (pinfunction "A_1") (pintype "input"))
      (node (ref "U3") (pin "24") (pinfunction "RB3/PGM_24") (pintype "input"))
    )
    (net (code "62") (name "Net-(R11-B)") (class "Default")
      (node (ref "D1") (pin "A") (pinfunction "A_A") (pintype "passive"))
      (node (ref "R11") (pin "2") (pinfunction "B_2") (pintype "passive"))
    )
    (net (code "63") (name "Net-(R13-A)") (class "Default")
      (node (ref "J5") (pin "1") (pinfunction "1_1") (pintype "passive"))
      (node (ref "R13") (pin "1") (pinfunction "A_1") (pintype "input"))
    )
    (net (code "64") (name "Net-(R14-A)") (class "Default")
      (node (ref "J5") (pin "4") (pinfunction "4_4") (pintype "passive"))
      (node (ref "R14") (pin "1") (pinfunction "A_1") (pintype "input"))
    )
    (net (code "65") (name "Net-(R15-A)") (class "Default")
      (node (ref "J5") (pin "7") (pinfunction "7_7") (pintype "passive"))
      (node (ref "R15") (pin "1") (pinfunction "A_1") (pintype "input"))
    )
    (net (code "66") (name "Net-(R16-A)") (class "Default")
      (node (ref "J5") (pin "9") (pinfunction "9_9") (pintype "passive"))
      (node (ref "R16") (pin "1") (pinfunction "A_1") (pintype "input"))
    )
    (net (code "67") (name "Net-(R17-A)") (class "Default")
      (node (ref "J5") (pin "10") (pinfunction "10_10") (pintype "passive"))
      (node (ref "R17") (pin "1") (pinfunction "A_1") (pintype "input"))
    )
    (net (code "68") (name "Net-(R18-B)") (class "Default")
      (node (ref "D3") (pin "A") (pinfunction "A_A") (pintype "passive"))
      (node (ref "R18") (pin "2") (pinfunction "B_2") (pintype "input"))
    )
    (net (code "69") (name "Net-(R19-B)") (class "Default")
      (node (ref "D2") (pin "A") (pinfunction "A_A") (pintype "passive"))
      (node (ref "R19") (pin "2") (pinfunction "B_2") (pintype "input"))
    )
    (net (code "70") (name "Net-(R20-B)") (class "Default")
      (node (ref "Q1") (pin "B") (pinfunction "B_B") (pintype "input"))
      (node (ref "R20") (pin "2") (pinfunction "B_2") (pintype "passive"))
    )
    (net (code "71") (name "Net-(R21-B)") (class "Default")
      (node (ref "Q2") (pin "B") (pinfunction "B_B") (pintype "input"))
      (node (ref "R21") (pin "2") (pinfunction "B_2") (pintype "passive"))
    )
    (net (code "72") (name "Net-(R22-B)") (class "Default")
      (node (ref "J5") (pin "5") (pinfunction "5_5") (pintype "passive"))
      (node (ref "R22") (pin "2") (pinfunction "B_2") (pintype "input"))
    )
    (net (code "73") (name "Net-(R23-A)") (class "Default")
      (node (ref "J5") (pin "6") (pinfunction "6_6") (pintype "passive"))
      (node (ref "R23") (pin "1") (pinfunction "A_1") (pintype "input"))
    )
    (net (code "74") (name "Net-(TP2-TP)") (class "Default")
      (node (ref "TP2") (pin "1") (pinfunction "TP_1") (pintype "passive"))
      (node (ref "U2") (pin "26") (pinfunction "RB5_26") (pintype "input"))
    )
    (net (code "75") (name "Net-(TP3-TP)") (class "Default")
      (node (ref "TP3") (pin "1") (pinfunction "TP_1") (pintype "passive"))
      (node (ref "U3") (pin "26") (pinfunction "RB5_26") (pintype "input"))
    )
    (net (code "76") (name "Net-(U4-R1OUT)") (class "Default")
      (node (ref "R204") (pin "1") (pinfunction "1_1") (pintype "passive"))
      (node (ref "U4") (pin "12") (pinfunction "R1OUT_12") (pintype "passive"))
    )
    (net (code "77") (name "Net-(U4-R2OUT)") (class "Default")
      (node (ref "U4") (pin "10") (pinfunction "T2IN_10") (pintype "passive"))
      (node (ref "U4") (pin "9") (pinfunction "R2OUT_9") (pintype "passive"))
    )
    (net (code "78") (name "Net-(U7-FB)") (class "Default")
      (node (ref "R30") (pin "1") (pinfunction "1_1") (pintype "passive"))
      (node (ref "R31") (pin "2") (pinfunction "2_2") (pintype "passive"))
      (node (ref "U7") (pin "3") (pinfunction "FB_3") (pintype "input"))
    )
    (net (code "79") (name "Net-(U7-SW)") (class "Default")
      (node (ref "D5") (pin "A") (pinfunction "A_A") (pintype "passive"))
      (node (ref "L2") (pin "2") (pinfunction "2_2") (pintype "passive"))
      (node (ref "U7") (pin "1") (pinfunction "SW_1") (pintype "input"))
    )
    (net (code "80") (name "Net-(U200-+)") (class "Default")
      (node (ref "J6") (pin "19") (pinfunction "19_19") (pintype "passive"))
      (node (ref "J6") (pin "38") (pinfunction "38_38") (pintype "passive"))
      (node (ref "U200") (pin "3") (pinfunction "+_3") (pintype "input"))
    )
    (net (code "81") (name "Net-(U200--)") (class "Default")
      (node (ref "R202") (pin "1") (pinfunction "1_1") (pintype "passive"))
      (node (ref "R203") (pin "2") (pinfunction "2_2") (pintype "passive"))
      (node (ref "U200") (pin "1") (pinfunction "-_1") (pintype "input"))
    )
    (net (code "82") (name "VCC") (class "Default")
      (node (ref "C1") (pin "1") (pinfunction "A_1") (pintype "input"))
      (node (ref "C2") (pin "1") (pinfunction "A_1") (pintype "input"))
      (node (ref "C25") (pin "1") (pinfunction "1_1") (pintype "passive"))
      (node (ref "C5") (pin "2") (pinfunction "B_2") (pintype "input"))
      (node (ref "C7") (pin "1") (pinfunction "A_1") (pintype "input"))
      (node (ref "C8") (pin "1") (pinfunction "A_1") (pintype "input"))
      (node (ref "C9") (pin "1") (pinfunction "A_1") (pintype "input"))
      (node (ref "D5") (pin "K") (pinfunction "K_K") (pintype "passive"))
      (node (ref "J5") (pin "8") (pinfunction "8_8") (pintype "passive"))
      (node (ref "R1") (pin "1") (pinfunction "A_1") (pintype "input"))
      (node (ref "R10") (pin "1") (pinfunction "A_1") (pintype "input"))
      (node (ref "R11") (pin "1") (pinfunction "A_1") (pintype "passive"))
      (node (ref "R18") (pin "1") (pinfunction "A_1") (pintype "input"))
      (node (ref "R19") (pin "1") (pinfunction "A_1") (pintype "input"))
      (node (ref "R202") (pin "2") (pinfunction "2_2") (pintype "passive"))
      (node (ref "R3") (pin "1") (pinfunction "A_1") (pintype "input"))
      (node (ref "R30") (pin "2") (pinfunction "2_2") (pintype "passive"))
      (node (ref "R5") (pin "1") (pinfunction "A_1") (pintype "input"))
      (node (ref "R9") (pin "1") (pinfunction "A_1") (pintype "input"))
      (node (ref "TP19") (pin "1") (pinfunction "TP_1") (pintype "passive"))
      (node (ref "U1") (pin "20") (pinfunction "Vdd_20") (pintype "input"))
      (node (ref "U2") (pin "20") (pinfunction "Vdd_20") (pintype "input"))
      (node (ref "U200") (pin "5") (pinfunction "VDD_5") (pintype "power_in"))
      (node (ref "U3") (pin "20") (pinfunction "Vdd_20") (pintype "input"))
      (node (ref "U4") (pin "16") (pinfunction "VCC_16") (pintype "passive"))
      (node (ref "U6") (pin "4") (pinfunction "VCC_4") (pintype "input"))
    )
    (net (code "83") (name "unconnected-(J6-Pad11)") (class "Default")
      (node (ref "J6") (pin "11") (pinfunction "11_11") (pintype "passive"))
    )
    (net (code "84") (name "unconnected-(J6-Pad12)") (class "Default")
      (node (ref "J6") (pin "12") (pinfunction "12_12") (pintype "passive"))
    )
    (net (code "85") (name "unconnected-(J6-Pad13)") (class "Default")
      (node (ref "J6") (pin "13") (pinfunction "13_13") (pintype "passive"))
    )
    (net (code "86") (name "unconnected-(J6-Pad14)") (class "Default")
      (node (ref "J6") (pin "14") (pinfunction "14_14") (pintype "passive"))
    )
    (net (code "87") (name "unconnected-(J6-Pad16)") (class "Default")
      (node (ref "J6") (pin "16") (pinfunction "16_16") (pintype "passive"))
    )
    (net (code "88") (name "unconnected-(J6-Pad17)") (class "Default")
      (node (ref "J6") (pin "17") (pinfunction "17_17") (pintype "passive"))
    )
    (net (code "89") (name "unconnected-(J6-Pad20)") (class "Default")
      (node (ref "J6") (pin "20") (pinfunction "20_20") (pintype "passive"))
    )
    (net (code "90") (name "unconnected-(J6-Pad24)") (class "Default")
      (node (ref "J6") (pin "24") (pinfunction "24_24") (pintype "passive"))
    )
    (net (code "91") (name "unconnected-(J6-Pad25)") (class "Default")
      (node (ref "J6") (pin "25") (pinfunction "25_25") (pintype "passive"))
    )
    (net (code "92") (name "unconnected-(J6-Pad26)") (class "Default")
      (node (ref "J6") (pin "26") (pinfunction "26_26") (pintype "passive"))
    )
    (net (code "93") (name "unconnected-(J6-Pad27)") (class "Default")
      (node (ref "J6") (pin "27") (pinfunction "27_27") (pintype "passive"))
    )
    (net (code "94") (name "unconnected-(J6-Pad28)") (class "Default")
      (node (ref "J6") (pin "28") (pinfunction "28_28") (pintype "passive"))
    )
    (net (code "95") (name "unconnected-(J6-Pad36)") (class "Default")
      (node (ref "J6") (pin "36") (pinfunction "36_36") (pintype "passive"))
    )
    (net (code "96") (name "unconnected-(J6-Pad39)") (class "Default")
      (node (ref "J6") (pin "39") (pinfunction "39_39") (pintype "passive"))
    )
    (net (code "97") (name "unconnected-(J6-Pad40)") (class "Default")
      (node (ref "J6") (pin "40") (pinfunction "40_40") (pintype "passive"))
    )
    (net (code "98") (name "unconnected-(U1-OSC2{slash}CLKOUT-Pad10)") (class "Default")
      (node (ref "U1") (pin "10") (pinfunction "OSC2/CLKOUT_10") (pintype "input"))
    )
    (net (code "99") (name "unconnected-(U2-OSC2{slash}CLKOUT-Pad10)") (class "Default")
      (node (ref "U2") (pin "10") (pinfunction "OSC2/CLKOUT_10") (pintype "input"))
    )
    (net (code "100") (name "unconnected-(U3-OSC2{slash}CLKOUT-Pad10)") (class "Default")
      (node (ref "U3") (pin "10") (pinfunction "OSC2/CLKOUT_10") (pintype "input"))
    )
    (net (code "101") (name "unconnected-(U3-RA2{slash}AN2{slash}Vref--Pad4)") (class "Default")
      (node (ref "U3") (pin "4") (pinfunction "RA2/AN2/Vref-_4") (pintype "input"))
    )
    (net (code "102") (name "unconnected-(U3-RA3{slash}AN3{slash}Vref+-Pad5)") (class "Default")
      (node (ref "U3") (pin "5") (pinfunction "RA3/AN3/Vref+_5") (pintype "input"))
    )
    (net (code "103") (name "unconnected-(U3-RA5{slash}AN4-Pad7)") (class "Default")
      (node (ref "U3") (pin "7") (pinfunction "RA5/AN4_7") (pintype "input"))
    )
    (net (code "104") (name "unconnected-(U3-RC0{slash}T1OSO{slash}T1CKI-Pad11)") (class "Default")
      (node (ref "U3") (pin "11") (pinfunction "RC0/T1OSO/T1CKI_11") (pintype "input"))
    )
    (net (code "105") (name "unconnected-(U3-RC1{slash}T1OSI-Pad12)") (class "Default")
      (node (ref "U3") (pin "12") (pinfunction "RC1/T1OSI_12") (pintype "input"))
    )
    (net (code "106") (name "unconnected-(U3-RC5-Pad16)") (class "Default")
      (node (ref "U3") (pin "16") (pinfunction "RC5_16") (pintype "input"))
    )
    (net (code "107") (name "unconnected-(U3-RC6{slash}TX{slash}CK-Pad17)") (class "Default")
      (node (ref "U3") (pin "17") (pinfunction "RC6/TX/CK_17") (pintype "input"))
    )
    (net (code "108") (name "unconnected-(U6-OE-Pad1)") (class "Default")
      (node (ref "U6") (pin "1") (pinfunction "OE_1") (pintype "input"))
    )
  )
)
